# OXCO_DaughterCard_Main.net
KiCad netlist of a schematic drawn in Altium Designer
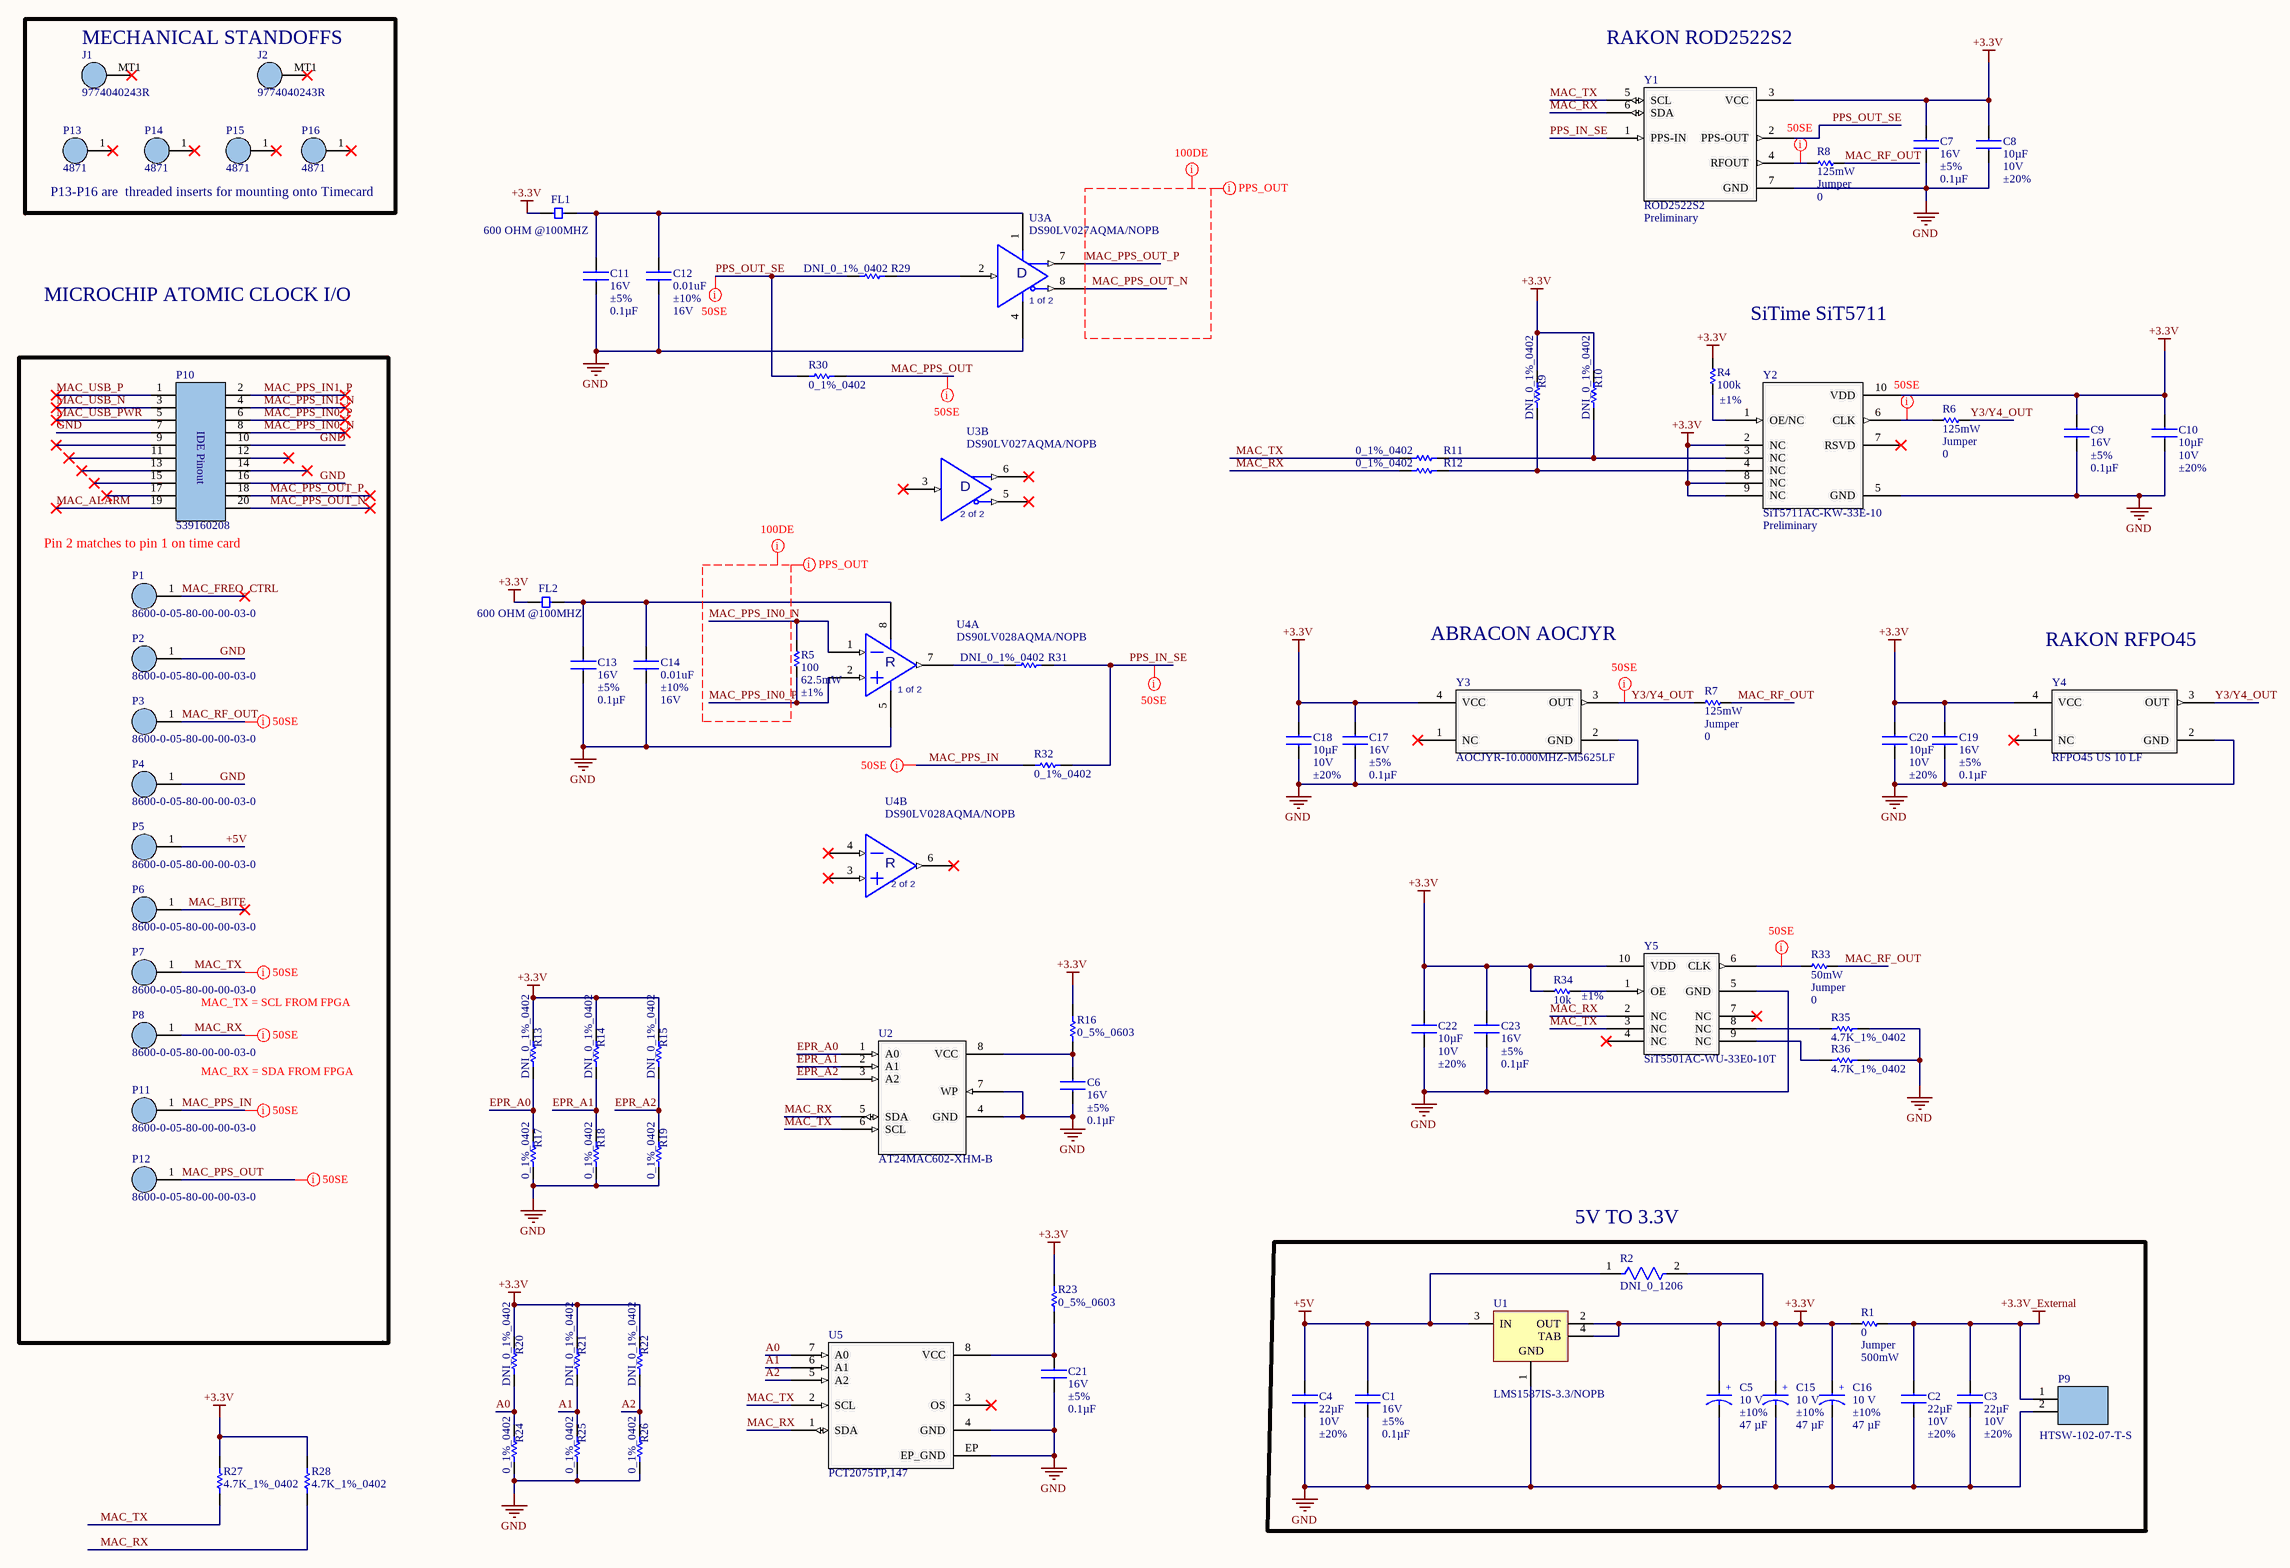
[diagram p0: OXCO_DaughterCard_Main.schdoc]

(export (version "E")
  (design (tool "Eeschema 10.0.6"))
  (components
    (comp (ref "C1")
      (value "Samsung Electro-Mechanics_CL05B104JO5NNNC")
      (footprint "CAPC1005X055N")
      (description "CAP, CER, X7R, 0.1UF, 5%, 16V, 0402, 0.55MM T")
      (fields
        (field (name "MANUFACTURER") "Samsung Electro-Mechanics")
        (field (name "VOLTAGE RATING") "16V")
        (field (name "TOLERANCE") "±5%")
        (field (name "MANUFACTURER PART NUMBER") "CL05B104JO5NNNC")
        (field (name "CAPACITANCE") "0.1µF")
      )
      (libsource (lib "FRL Altium Server") (part "Capacitor_300mil"))
    )
    (comp (ref "C2")
      (value "Murata_GRM21BR61A226ME51L")
      (footprint "CAPC2013X140N")
      (description "CAP, CER, X5R, 22UF, 20%, 10V, 0805, 1.40MM T")
      (fields
        (field (name "CAPACITANCE") "22µF")
        (field (name "VOLTAGE RATING") "10V")
        (field (name "MANUFACTURER PART NUMBER") "GRM21BR61A226ME51L")
        (field (name "TOLERANCE") "±20%")
        (field (name "MANUFACTURER") "Murata")
      )
      (libsource (lib "FRL Altium Server") (part "Capacitor_300mil"))
    )
    (comp (ref "C3")
      (value "Murata_GRM21BR61A226ME51L")
      (footprint "CAPC2013X140N")
      (description "CAP, CER, X5R, 22UF, 20%, 10V, 0805, 1.40MM T")
      (fields
        (field (name "CAPACITANCE") "22µF")
        (field (name "VOLTAGE RATING") "10V")
        (field (name "MANUFACTURER PART NUMBER") "GRM21BR61A226ME51L")
        (field (name "TOLERANCE") "±20%")
        (field (name "MANUFACTURER") "Murata")
      )
      (libsource (lib "FRL Altium Server") (part "Capacitor_300mil"))
    )
    (comp (ref "C4")
      (value "Murata_GRM21BR61A226ME51L")
      (footprint "CAPC2013X140N")
      (description "CAP, CER, X5R, 22UF, 20%, 10V, 0805, 1.40MM T")
      (fields
        (field (name "CAPACITANCE") "22µF")
        (field (name "VOLTAGE RATING") "10V")
        (field (name "MANUFACTURER PART NUMBER") "GRM21BR61A226ME51L")
        (field (name "TOLERANCE") "±20%")
        (field (name "MANUFACTURER") "Murata")
      )
      (libsource (lib "FRL Altium Server") (part "Capacitor_300mil"))
    )
    (comp (ref "C5")
      (value "Kemet_T491B476K010AT")
      (footprint "CAPMP3528X210N_T520")
      (description "CAP TANT 47UF 10% 10V 1411")
      (fields
        (field (name "VOLTAGE RATING") "10 V")
        (field (name "MANUFACTURER PART NUMBER") "T491B476K010AT")
        (field (name "TOLERANCE") "±10%")
        (field (name "CAPACITANCE") "47 µF")
        (field (name "MANUFACTURER") "Kemet")
      )
      (libsource (lib "FRL Altium Server") (part "Capacitor_Polar_300mil"))
    )
    (comp (ref "C6")
      (value "Samsung Electro-Mechanics_CL05B104JO5NNNC")
      (footprint "CAPC1005X055N")
      (description "CAP, CER, X7R, 0.1UF, 5%, 16V, 0402, 0.55MM T")
      (fields
        (field (name "MANUFACTURER") "Samsung Electro-Mechanics")
        (field (name "VOLTAGE RATING") "16V")
        (field (name "TOLERANCE") "±5%")
        (field (name "MANUFACTURER PART NUMBER") "CL05B104JO5NNNC")
        (field (name "CAPACITANCE") "0.1µF")
      )
      (libsource (lib "FRL Altium Server") (part "Capacitor_300mil"))
    )
    (comp (ref "C7")
      (value "Samsung Electro-Mechanics_CL05B104JO5NNNC")
      (footprint "CAPC1005X055N")
      (description "CAP, CER, X7R, 0.1UF, 5%, 16V, 0402, 0.55MM T")
      (fields
        (field (name "MANUFACTURER") "Samsung Electro-Mechanics")
        (field (name "VOLTAGE RATING") "16V")
        (field (name "TOLERANCE") "±5%")
        (field (name "MANUFACTURER PART NUMBER") "CL05B104JO5NNNC")
        (field (name "CAPACITANCE") "0.1µF")
      )
      (libsource (lib "FRL Altium Server") (part "Capacitor_300mil"))
    )
    (comp (ref "C8")
      (value "Murata_GRM188D71A106MA73D")
      (footprint "CAPC1608X100N")
      (description "CAP, CER, X7T, 10UF, 20%, 10V, 0603, 1.00MM T")
      (fields
        (field (name "MANUFACTURER PART NUMBER") "GRM188D71A106MA73D")
        (field (name "CAPACITANCE") "10µF")
        (field (name "VOLTAGE RATING") "10V")
        (field (name "MANUFACTURER") "Murata")
        (field (name "TOLERANCE") "±20%")
      )
      (libsource (lib "FRL Altium Server") (part "Capacitor_300mil"))
    )
    (comp (ref "C9")
      (value "Samsung Electro-Mechanics_CL05B104JO5NNNC")
      (footprint "CAPC1005X055N")
      (description "CAP, CER, X7R, 0.1UF, 5%, 16V, 0402, 0.55MM T")
      (fields
        (field (name "MANUFACTURER") "Samsung Electro-Mechanics")
        (field (name "VOLTAGE RATING") "16V")
        (field (name "TOLERANCE") "±5%")
        (field (name "MANUFACTURER PART NUMBER") "CL05B104JO5NNNC")
        (field (name "CAPACITANCE") "0.1µF")
      )
      (libsource (lib "FRL Altium Server") (part "Capacitor_300mil"))
    )
    (comp (ref "C10")
      (value "Murata_GRM188D71A106MA73D")
      (footprint "CAPC1608X100N")
      (description "CAP, CER, X7T, 10UF, 20%, 10V, 0603, 1.00MM T")
      (fields
        (field (name "MANUFACTURER PART NUMBER") "GRM188D71A106MA73D")
        (field (name "CAPACITANCE") "10µF")
        (field (name "VOLTAGE RATING") "10V")
        (field (name "MANUFACTURER") "Murata")
        (field (name "TOLERANCE") "±20%")
      )
      (libsource (lib "FRL Altium Server") (part "Capacitor_300mil"))
    )
    (comp (ref "C11")
      (value "Samsung Electro-Mechanics_CL05B104JO5NNNC")
      (footprint "CAPC1005X055N")
      (description "CAP, CER, X7R, 0.1UF, 5%, 16V, 0402, 0.55MM T")
      (fields
        (field (name "MANUFACTURER") "Samsung Electro-Mechanics")
        (field (name "VOLTAGE RATING") "16V")
        (field (name "TOLERANCE") "±5%")
        (field (name "MANUFACTURER PART NUMBER") "CL05B104JO5NNNC")
        (field (name "CAPACITANCE") "0.1µF")
      )
      (libsource (lib "FRL Altium Server") (part "Capacitor_300mil"))
    )
    (comp (ref "C12")
      (value "Yageo_CC0402KRX7R7BB103")
      (footprint "CAPC1005X055N")
      (description "CAP, CER, X7R, 0.01UF, 10%, 16V, 0402, 0.55MM T")
      (fields
        (field (name "MANUFACTURER") "Yageo")
        (field (name "CAPACITANCE") "0.01uF")
        (field (name "TOLERANCE") "±10%")
        (field (name "MANUFACTURER PART NUMBER") "CC0402KRX7R7BB103")
        (field (name "VOLTAGE RATING") "16V")
      )
      (libsource (lib "FRL Altium Server") (part "Capacitor_300mil"))
    )
    (comp (ref "C13")
      (value "Samsung Electro-Mechanics_CL05B104JO5NNNC")
      (footprint "CAPC1005X055N")
      (description "CAP, CER, X7R, 0.1UF, 5%, 16V, 0402, 0.55MM T")
      (fields
        (field (name "MANUFACTURER") "Samsung Electro-Mechanics")
        (field (name "VOLTAGE RATING") "16V")
        (field (name "TOLERANCE") "±5%")
        (field (name "MANUFACTURER PART NUMBER") "CL05B104JO5NNNC")
        (field (name "CAPACITANCE") "0.1µF")
      )
      (libsource (lib "FRL Altium Server") (part "Capacitor_300mil"))
    )
    (comp (ref "C14")
      (value "Yageo_CC0402KRX7R7BB103")
      (footprint "CAPC1005X055N")
      (description "CAP, CER, X7R, 0.01UF, 10%, 16V, 0402, 0.55MM T")
      (fields
        (field (name "MANUFACTURER") "Yageo")
        (field (name "CAPACITANCE") "0.01uF")
        (field (name "TOLERANCE") "±10%")
        (field (name "MANUFACTURER PART NUMBER") "CC0402KRX7R7BB103")
        (field (name "VOLTAGE RATING") "16V")
      )
      (libsource (lib "FRL Altium Server") (part "Capacitor_300mil"))
    )
    (comp (ref "C15")
      (value "Kemet_T491B476K010AT")
      (footprint "CAPMP3528X210N_T520")
      (description "CAP TANT 47UF 10% 10V 1411")
      (fields
        (field (name "VOLTAGE RATING") "10 V")
        (field (name "MANUFACTURER PART NUMBER") "T491B476K010AT")
        (field (name "TOLERANCE") "±10%")
        (field (name "CAPACITANCE") "47 µF")
        (field (name "MANUFACTURER") "Kemet")
      )
      (libsource (lib "FRL Altium Server") (part "Capacitor_Polar_300mil"))
    )
    (comp (ref "C16")
      (value "Kemet_T491B476K010AT")
      (footprint "CAPMP3528X210N_T520")
      (description "CAP TANT 47UF 10% 10V 1411")
      (fields
        (field (name "VOLTAGE RATING") "10 V")
        (field (name "MANUFACTURER PART NUMBER") "T491B476K010AT")
        (field (name "TOLERANCE") "±10%")
        (field (name "CAPACITANCE") "47 µF")
        (field (name "MANUFACTURER") "Kemet")
      )
      (libsource (lib "FRL Altium Server") (part "Capacitor_Polar_300mil"))
    )
    (comp (ref "C17")
      (value "Samsung Electro-Mechanics_CL05B104JO5NNNC")
      (footprint "CAPC1005X055N")
      (description "CAP, CER, X7R, 0.1UF, 5%, 16V, 0402, 0.55MM T")
      (fields
        (field (name "MANUFACTURER") "Samsung Electro-Mechanics")
        (field (name "VOLTAGE RATING") "16V")
        (field (name "TOLERANCE") "±5%")
        (field (name "MANUFACTURER PART NUMBER") "CL05B104JO5NNNC")
        (field (name "CAPACITANCE") "0.1µF")
      )
      (libsource (lib "FRL Altium Server") (part "Capacitor_300mil"))
    )
    (comp (ref "C18")
      (value "Murata_GRM188D71A106MA73D")
      (footprint "CAPC1608X100N")
      (description "CAP, CER, X7T, 10UF, 20%, 10V, 0603, 1.00MM T")
      (fields
        (field (name "MANUFACTURER PART NUMBER") "GRM188D71A106MA73D")
        (field (name "CAPACITANCE") "10µF")
        (field (name "VOLTAGE RATING") "10V")
        (field (name "MANUFACTURER") "Murata")
        (field (name "TOLERANCE") "±20%")
      )
      (libsource (lib "FRL Altium Server") (part "Capacitor_300mil"))
    )
    (comp (ref "C19")
      (value "Samsung Electro-Mechanics_CL05B104JO5NNNC")
      (footprint "CAPC1005X055N")
      (description "CAP, CER, X7R, 0.1UF, 5%, 16V, 0402, 0.55MM T")
      (fields
        (field (name "MANUFACTURER") "Samsung Electro-Mechanics")
        (field (name "VOLTAGE RATING") "16V")
        (field (name "TOLERANCE") "±5%")
        (field (name "MANUFACTURER PART NUMBER") "CL05B104JO5NNNC")
        (field (name "CAPACITANCE") "0.1µF")
      )
      (libsource (lib "FRL Altium Server") (part "Capacitor_300mil"))
    )
    (comp (ref "C20")
      (value "Murata_GRM188D71A106MA73D")
      (footprint "CAPC1608X100N")
      (description "CAP, CER, X7T, 10UF, 20%, 10V, 0603, 1.00MM T")
      (fields
        (field (name "MANUFACTURER PART NUMBER") "GRM188D71A106MA73D")
        (field (name "CAPACITANCE") "10µF")
        (field (name "VOLTAGE RATING") "10V")
        (field (name "MANUFACTURER") "Murata")
        (field (name "TOLERANCE") "±20%")
      )
      (libsource (lib "FRL Altium Server") (part "Capacitor_300mil"))
    )
    (comp (ref "C21")
      (value "Samsung Electro-Mechanics_CL05B104JO5NNNC")
      (footprint "CAPC1005X055N")
      (description "CAP, CER, X7R, 0.1UF, 5%, 16V, 0402, 0.55MM T")
      (fields
        (field (name "MANUFACTURER") "Samsung Electro-Mechanics")
        (field (name "VOLTAGE RATING") "16V")
        (field (name "TOLERANCE") "±5%")
        (field (name "MANUFACTURER PART NUMBER") "CL05B104JO5NNNC")
        (field (name "CAPACITANCE") "0.1µF")
      )
      (libsource (lib "FRL Altium Server") (part "Capacitor_300mil"))
    )
    (comp (ref "C22")
      (value "Murata_GRM188R61A106ME69D")
      (footprint "CAPC1608X090N")
      (description "CAP, CER, X5R, 10UF, 20%, 10V, 0603, 0.80MM T")
      (fields
        (field (name "MANUFACTURER PART NUMBER") "GRM188R61A106ME69D")
        (field (name "CAPACITANCE") "10µF")
        (field (name "VOLTAGE RATING") "10V")
        (field (name "MANUFACTURER") "Murata")
        (field (name "TOLERANCE") "±20%")
      )
      (libsource (lib "Meta RLR Altium Enterprise Server") (part "Capacitor_300mil"))
    )
    (comp (ref "C23")
      (value "Samsung Electro-Mechanics_CL05B104JO5NNNC")
      (footprint "CAPC1005X055N")
      (description "CAP, CER, X7R, 0.1UF, 5%, 16V, 0402, 0.55MM T")
      (fields
        (field (name "MANUFACTURER") "Samsung Electro-Mechanics")
        (field (name "VOLTAGE RATING") "16V")
        (field (name "TOLERANCE") "±5%")
        (field (name "MANUFACTURER PART NUMBER") "CL05B104JO5NNNC")
        (field (name "CAPACITANCE") "0.1µF")
      )
      (libsource (lib "Meta RLR Altium Enterprise Server") (part "Capacitor_300mil"))
    )
    (comp (ref "FL1")
      (value "TDK_MPZ1608S601ATA00")
      (footprint "INDC1608X095N")
      (description "FERRITE BEAD, 600 OHM @100MHZ, 25%, 1A, 0.150 OHM DCR, 0603, 0.95MM T")
      (fields
        (field (name "MANUFACTURER PART NUMBER") "MPZ1608S601ATA00")
        (field (name "TOLERANCE") "0.25%")
        (field (name "IMPEDANCE @ FREQUENCY") "600 OHM @100MHZ")
      )
      (libsource (lib "FRL Altium Server") (part "FerriteBead_300mil"))
    )
    (comp (ref "FL2")
      (value "TDK_MPZ1608S601ATA00")
      (footprint "INDC1608X095N")
      (description "FERRITE BEAD, 600 OHM @100MHZ, 25%, 1A, 0.150 OHM DCR, 0603, 0.95MM T")
      (fields
        (field (name "MANUFACTURER PART NUMBER") "MPZ1608S601ATA00")
        (field (name "TOLERANCE") "0.25%")
        (field (name "IMPEDANCE @ FREQUENCY") "600 OHM @100MHZ")
      )
      (libsource (lib "FRL Altium Server") (part "FerriteBead_300mil"))
    )
    (comp (ref "J1")
      (value "Wurth_9774040243R")
      (footprint "TH000V_300DIAx400_001mt_9774040243R")
      (description "STANDOFF, ROUND, M2X0.4 STEEL 4MM, 9774040243R")
      (fields
        (field (name "MANUFACTURER PART NUMBER") "9774040243R")
        (field (name "MANUFACTURER") "Wurth Elektronik")
      )
      (libsource (lib "FRL Altium Server") (part "CONN_SR_000pin_001mt_RND_F"))
    )
    (comp (ref "J2")
      (value "Wurth_9774040243R")
      (footprint "TH000V_300DIAx400_001mt_9774040243R")
      (description "STANDOFF, ROUND, M2X0.4 STEEL 4MM, 9774040243R")
      (fields
        (field (name "MANUFACTURER PART NUMBER") "9774040243R")
        (field (name "MANUFACTURER") "Wurth Elektronik")
      )
      (libsource (lib "FRL Altium Server") (part "CONN_SR_000pin_001mt_RND_F"))
    )
    (comp (ref "P1")
      (value "Mill-Max_8600-0-05-80-00-00-03-0")
      (footprint "TH001V_109DIA_000mt_8600-0")
      (description "CONN, PC PIN, PRESS-FIT, 10.16MM LENGTH, TIN, TH")
      (fields
        (field (name "MANUFACTURER PART NUMBER") "8600-0-05-80-00-00-03-0")
        (field (name "MANUFACTURER") "Mill-Max Manufacturing Corp.")
      )
      (libsource (lib "FRL Altium Server") (part "CONN_SR_001pin_000mt_RND_M"))
    )
    (comp (ref "P2")
      (value "Mill-Max_8600-0-05-80-00-00-03-0")
      (footprint "TH001V_109DIA_000mt_8600-0")
      (description "CONN, PC PIN, PRESS-FIT, 10.16MM LENGTH, TIN, TH")
      (fields
        (field (name "MANUFACTURER PART NUMBER") "8600-0-05-80-00-00-03-0")
        (field (name "MANUFACTURER") "Mill-Max Manufacturing Corp.")
      )
      (libsource (lib "FRL Altium Server") (part "CONN_SR_001pin_000mt_RND_M"))
    )
    (comp (ref "P3")
      (value "Mill-Max_8600-0-05-80-00-00-03-0")
      (footprint "TH001V_109DIA_000mt_8600-0")
      (description "CONN, PC PIN, PRESS-FIT, 10.16MM LENGTH, TIN, TH")
      (fields
        (field (name "MANUFACTURER PART NUMBER") "8600-0-05-80-00-00-03-0")
        (field (name "MANUFACTURER") "Mill-Max Manufacturing Corp.")
      )
      (libsource (lib "FRL Altium Server") (part "CONN_SR_001pin_000mt_RND_M"))
    )
    (comp (ref "P4")
      (value "Mill-Max_8600-0-05-80-00-00-03-0")
      (footprint "TH001V_109DIA_000mt_8600-0")
      (description "CONN, PC PIN, PRESS-FIT, 10.16MM LENGTH, TIN, TH")
      (fields
        (field (name "MANUFACTURER PART NUMBER") "8600-0-05-80-00-00-03-0")
        (field (name "MANUFACTURER") "Mill-Max Manufacturing Corp.")
      )
      (libsource (lib "FRL Altium Server") (part "CONN_SR_001pin_000mt_RND_M"))
    )
    (comp (ref "P5")
      (value "Mill-Max_8600-0-05-80-00-00-03-0")
      (footprint "TH001V_109DIA_000mt_8600-0")
      (description "CONN, PC PIN, PRESS-FIT, 10.16MM LENGTH, TIN, TH")
      (fields
        (field (name "MANUFACTURER PART NUMBER") "8600-0-05-80-00-00-03-0")
        (field (name "MANUFACTURER") "Mill-Max Manufacturing Corp.")
      )
      (libsource (lib "FRL Altium Server") (part "CONN_SR_001pin_000mt_RND_M"))
    )
    (comp (ref "P6")
      (value "Mill-Max_8600-0-05-80-00-00-03-0")
      (footprint "TH001V_109DIA_000mt_8600-0")
      (description "CONN, PC PIN, PRESS-FIT, 10.16MM LENGTH, TIN, TH")
      (fields
        (field (name "MANUFACTURER PART NUMBER") "8600-0-05-80-00-00-03-0")
        (field (name "MANUFACTURER") "Mill-Max Manufacturing Corp.")
      )
      (libsource (lib "FRL Altium Server") (part "CONN_SR_001pin_000mt_RND_M"))
    )
    (comp (ref "P7")
      (value "Mill-Max_8600-0-05-80-00-00-03-0")
      (footprint "TH001V_109DIA_000mt_8600-0")
      (description "CONN, PC PIN, PRESS-FIT, 10.16MM LENGTH, TIN, TH")
      (fields
        (field (name "MANUFACTURER PART NUMBER") "8600-0-05-80-00-00-03-0")
        (field (name "MANUFACTURER") "Mill-Max Manufacturing Corp.")
      )
      (libsource (lib "FRL Altium Server") (part "CONN_SR_001pin_000mt_RND_M"))
    )
    (comp (ref "P8")
      (value "Mill-Max_8600-0-05-80-00-00-03-0")
      (footprint "TH001V_109DIA_000mt_8600-0")
      (description "CONN, PC PIN, PRESS-FIT, 10.16MM LENGTH, TIN, TH")
      (fields
        (field (name "MANUFACTURER PART NUMBER") "8600-0-05-80-00-00-03-0")
        (field (name "MANUFACTURER") "Mill-Max Manufacturing Corp.")
      )
      (libsource (lib "FRL Altium Server") (part "CONN_SR_001pin_000mt_RND_M"))
    )
    (comp (ref "P9")
      (value "Samtec_HTSW-102-07-T-S")
      (footprint "TH002_254_508x254x838_000mt_HTSW")
      (description "CONN, PIN, HEADER, 2POS, 2.54MM PITCH, 8.38MM H, VERT, TIN, TH")
      (fields
        (field (name "MANUFACTURER") "Samtec Inc.")
        (field (name "MANUFACTURER PART NUMBER") "HTSW-102-07-T-S")
      )
      (libsource (lib "FRL Altium Server") (part "CONN_SR_002pin_000mt_M"))
    )
    (comp (ref "P10")
      (value "Molex_539160208")
      (footprint "SM020V_50_730x310x337_000mt_53916")
      (description "CONN, B2B/FPC, HEADER, 20-POS, 0.5MM PITCH, 4.0MM H, VERT, GOLD, SMT")
      (fields (field (name "MANUFACTURER") "Molex") (field (name "MANUFACTURER PART NUMBER") "539160208"))
      (libsource (lib "FRL Altium Server") (part "CONN_DR_020pin_000mt_M"))
    )
    (comp (ref "P11")
      (value "Mill-Max_8600-0-05-80-00-00-03-0")
      (footprint "TH001V_109DIA_000mt_8600-0")
      (description "CONN, PC PIN, PRESS-FIT, 10.16MM LENGTH, TIN, TH")
      (fields
        (field (name "MANUFACTURER PART NUMBER") "8600-0-05-80-00-00-03-0")
        (field (name "MANUFACTURER") "Mill-Max Manufacturing Corp.")
      )
      (libsource (lib "FRL Altium Server") (part "CONN_SR_001pin_000mt_RND_M"))
    )
    (comp (ref "P12")
      (value "Mill-Max_8600-0-05-80-00-00-03-0")
      (footprint "TH001V_109DIA_000mt_8600-0")
      (description "CONN, PC PIN, PRESS-FIT, 10.16MM LENGTH, TIN, TH")
      (fields
        (field (name "MANUFACTURER PART NUMBER") "8600-0-05-80-00-00-03-0")
        (field (name "MANUFACTURER") "Mill-Max Manufacturing Corp.")
      )
      (libsource (lib "FRL Altium Server") (part "CONN_SR_001pin_000mt_RND_M"))
    )
    (comp (ref "P13")
      (value "4871")
      (footprint "Keystone_4871")
      (description "Round Standoff Threaded #2-56 Steel 0.063\" (1.60mm) 1/16\"")
      (fields (field (name "MANUFACTURER") "Keystone") (field (name "MANUFACTURER PART NUMBER") "4871"))
      (libsource (lib "846-01710_SCH_OCXO_DaughterCard") (part "Keystone_4871"))
    )
    (comp (ref "P14")
      (value "4871")
      (footprint "Keystone_4871")
      (description "Round Standoff Threaded #2-56 Steel 0.063\" (1.60mm) 1/16\"")
      (fields (field (name "MANUFACTURER") "Keystone") (field (name "MANUFACTURER PART NUMBER") "4871"))
      (libsource (lib "846-01710_SCH_OCXO_DaughterCard") (part "Keystone_4871"))
    )
    (comp (ref "P15")
      (value "4871")
      (footprint "Keystone_4871")
      (description "Round Standoff Threaded #2-56 Steel 0.063\" (1.60mm) 1/16\"")
      (fields (field (name "MANUFACTURER") "Keystone") (field (name "MANUFACTURER PART NUMBER") "4871"))
      (libsource (lib "846-01710_SCH_OCXO_DaughterCard") (part "Keystone_4871"))
    )
    (comp (ref "P16")
      (value "4871")
      (footprint "Keystone_4871")
      (description "Round Standoff Threaded #2-56 Steel 0.063\" (1.60mm) 1/16\"")
      (fields (field (name "MANUFACTURER") "Keystone") (field (name "MANUFACTURER PART NUMBER") "4871"))
      (libsource (lib "846-01710_SCH_OCXO_DaughterCard") (part "Keystone_4871"))
    )
    (comp (ref "R1")
      (value "Stackpole Electronics, Inc._RMCF1210ZT0R00")
      (footprint "RESC3225X070N")
      (description "RES, 0.0 OHM, 3A, 1/2W, 1210")
      (fields
        (field (name "MANUFACTURER PART NUMBER") "RMCF1210ZT0R00")
        (field (name "MANUFACTURER") "Stackpole Electronics, Inc.")
        (field (name "RESISTANCE") "0")
        (field (name "TOLERANCE") "Jumper")
        (field (name "POWER (WATTS)") "500mW")
      )
      (libsource (lib "FRL Altium Server") (part "Resistor_300mil"))
    )
    (comp (ref "R2")
      (value "DNI_0_1206")
      (footprint "FP-RC1206-MFG")
      (description "RES SMD 0 OHM JUMPER 1/4W 1206")
      (fields
        (field (name "MANUFACTURER PART NUMBER") "RC1206JR-070RL")
        (field (name "MANUFACTURER") "YAGEO")
      )
      (libsource (lib "Altium Content Vault") (part "1029c3af85768c4190bb7ad29bc67b5"))
    )
    (comp (ref "R4")
      (value "Panasonic_ERJ-2RKF1003X")
      (footprint "RESC1005X040N")
      (description "RES, 100K OHM, 1%, 1/10W, 100PPM/C, 0402")
      (fields
        (field (name "MANUFACTURER PART NUMBER") "ERJ-2RKF1003X")
        (field (name "MANUFACTURER") "Panasonic")
        (field (name "RESISTANCE") "100k")
        (field (name "TOLERANCE") "±1%")
      )
      (libsource (lib "FRL Altium Server") (part "Resistor_300mil"))
    )
    (comp (ref "R5")
      (value "Yageo_RC0402FR-07100RL")
      (footprint "RESC1005X040N")
      (description "RES SMD 100 OHM 1% 1/16W 0402")
      (fields
        (field (name "MANUFACTURER PART NUMBER") "RC0402FR-07100RL")
        (field (name "RESISTANCE") "100")
        (field (name "POWER (WATTS)") "62.5mW")
        (field (name "MANUFACTURER") "Yageo")
        (field (name "TOLERANCE") "±1%")
      )
      (libsource (lib "FRL Altium Server") (part "Resistor_300mil"))
    )
    (comp (ref "R6")
      (value "Stackpole Electronics, Inc._HCJ0402ZT0R00")
      (footprint "RESC1005X045N")
      (description "RES, 0.0 OHM, 1/8W, 6.5A, 0402")
      (fields
        (field (name "POWER (WATTS)") "125mW")
        (field (name "MANUFACTURER PART NUMBER") "HCJ0402ZT0R00")
        (field (name "TOLERANCE") "Jumper")
        (field (name "MANUFACTURER") "Stackpole Electronics, Inc.")
        (field (name "RESISTANCE") "0")
      )
      (libsource (lib "FRL Altium Server") (part "Resistor_300mil"))
    )
    (comp (ref "R7")
      (value "Stackpole Electronics, Inc._HCJ0402ZT0R00")
      (footprint "RESC1005X045N")
      (description "RES, 0.0 OHM, 1/8W, 6.5A, 0402")
      (fields
        (field (name "POWER (WATTS)") "125mW")
        (field (name "MANUFACTURER PART NUMBER") "HCJ0402ZT0R00")
        (field (name "TOLERANCE") "Jumper")
        (field (name "MANUFACTURER") "Stackpole Electronics, Inc.")
        (field (name "RESISTANCE") "0")
      )
      (libsource (lib "FRL Altium Server") (part "Resistor_300mil"))
    )
    (comp (ref "R8")
      (value "Stackpole Electronics, Inc._HCJ0402ZT0R00")
      (footprint "RESC1005X045N")
      (description "RES, 0.0 OHM, 1/8W, 6.5A, 0402")
      (fields
        (field (name "POWER (WATTS)") "125mW")
        (field (name "MANUFACTURER PART NUMBER") "HCJ0402ZT0R00")
        (field (name "TOLERANCE") "Jumper")
        (field (name "MANUFACTURER") "Stackpole Electronics, Inc.")
        (field (name "RESISTANCE") "0")
      )
      (libsource (lib "FRL Altium Server") (part "Resistor_300mil"))
    )
    (comp (ref "R9")
      (value "DNI_0_1%_0402")
      (footprint "RESC1005X40X25NL05T10")
      (fields (field (name "MANUFACTURER") "Yageo / Phycomp") (field (name "PART NUMBER") "RC0402JR-070RL"))
      (libsource (lib "Altium Content Vault") (part "RES"))
    )
    (comp (ref "R10")
      (value "DNI_0_1%_0402")
      (footprint "RESC1005X40X25NL05T10")
      (fields (field (name "MANUFACTURER") "Yageo / Phycomp") (field (name "PART NUMBER") "RC0402JR-070RL"))
      (libsource (lib "Altium Content Vault") (part "RES"))
    )
    (comp (ref "R11")
      (value "0_1%_0402")
      (footprint "RESC1005X40X25NL05T10")
      (fields (field (name "MANUFACTURER") "Yageo / Phycomp") (field (name "PART NUMBER") "RC0402JR-070RL"))
      (libsource (lib "Altium Content Vault") (part "RES"))
    )
    (comp (ref "R12")
      (value "0_1%_0402")
      (footprint "RESC1005X40X25NL05T10")
      (fields (field (name "MANUFACTURER") "Yageo / Phycomp") (field (name "PART NUMBER") "RC0402JR-070RL"))
      (libsource (lib "Altium Content Vault") (part "RES"))
    )
    (comp (ref "R13")
      (value "DNI_0_1%_0402")
      (footprint "RESC1005X40X25NL05T10")
      (fields (field (name "MANUFACTURER") "Yageo / Phycomp") (field (name "PART NUMBER") "RC0402JR-070RL"))
      (libsource (lib "Altium Content Vault") (part "RES"))
    )
    (comp (ref "R14")
      (value "DNI_0_1%_0402")
      (footprint "RESC1005X40X25NL05T10")
      (fields (field (name "MANUFACTURER") "Yageo / Phycomp") (field (name "PART NUMBER") "RC0402JR-070RL"))
      (libsource (lib "Altium Content Vault") (part "RES"))
    )
    (comp (ref "R15")
      (value "DNI_0_1%_0402")
      (footprint "RESC1005X40X25NL05T10")
      (fields (field (name "MANUFACTURER") "Yageo / Phycomp") (field (name "PART NUMBER") "RC0402JR-070RL"))
      (libsource (lib "Altium Content Vault") (part "RES"))
    )
    (comp (ref "R16")
      (value "0_5%_0603")
      (footprint "RESC1608X55X25ML10T15")
      (description "Chip Resistor, 0 Ohm, +/- 5%, 0.1 W, -55 to 155 degC, 0603 (1608 Metric), RoHS, Tape and Reel")
      (fields (field (name "TOLERANCE") "5%") (field (name "MANUFACTURER") "Yageo"))
      (libsource (lib "Altium Content Vault") (part "RES-2"))
    )
    (comp (ref "R17")
      (value "0_1%_0402")
      (footprint "RESC1005X40X25NL05T10")
      (fields (field (name "MANUFACTURER") "Yageo / Phycomp") (field (name "PART NUMBER") "RC0402JR-070RL"))
      (libsource (lib "Altium Content Vault") (part "RES"))
    )
    (comp (ref "R18")
      (value "0_1%_0402")
      (footprint "RESC1005X40X25NL05T10")
      (fields (field (name "MANUFACTURER") "Yageo / Phycomp") (field (name "PART NUMBER") "RC0402JR-070RL"))
      (libsource (lib "Altium Content Vault") (part "RES"))
    )
    (comp (ref "R19")
      (value "0_1%_0402")
      (footprint "RESC1005X40X25NL05T10")
      (fields (field (name "MANUFACTURER") "Yageo / Phycomp") (field (name "PART NUMBER") "RC0402JR-070RL"))
      (libsource (lib "Altium Content Vault") (part "RES"))
    )
    (comp (ref "R20")
      (value "DNI_0_1%_0402")
      (footprint "RESC1005X40X25NL05T10")
      (fields (field (name "MANUFACTURER") "Yageo / Phycomp") (field (name "PART NUMBER") "RC0402JR-070RL"))
      (libsource (lib "Altium Content Vault") (part "RES"))
    )
    (comp (ref "R21")
      (value "DNI_0_1%_0402")
      (footprint "RESC1005X40X25NL05T10")
      (fields (field (name "MANUFACTURER") "Yageo / Phycomp") (field (name "PART NUMBER") "RC0402JR-070RL"))
      (libsource (lib "Altium Content Vault") (part "RES"))
    )
    (comp (ref "R22")
      (value "DNI_0_1%_0402")
      (footprint "RESC1005X40X25NL05T10")
      (fields (field (name "MANUFACTURER") "Yageo / Phycomp") (field (name "PART NUMBER") "RC0402JR-070RL"))
      (libsource (lib "Altium Content Vault") (part "RES"))
    )
    (comp (ref "R23")
      (value "0_5%_0603")
      (footprint "RESC1608X55X25ML10T15")
      (description "Chip Resistor, 0 Ohm, +/- 5%, 0.1 W, -55 to 155 degC, 0603 (1608 Metric), RoHS, Tape and Reel")
      (fields (field (name "TOLERANCE") "5%") (field (name "MANUFACTURER") "Yageo"))
      (libsource (lib "Altium Content Vault") (part "RES-2"))
    )
    (comp (ref "R24")
      (value "0_1%_0402")
      (footprint "RESC1005X40X25NL05T10")
      (fields (field (name "MANUFACTURER") "Yageo / Phycomp") (field (name "PART NUMBER") "RC0402JR-070RL"))
      (libsource (lib "Altium Content Vault") (part "RES"))
    )
    (comp (ref "R25")
      (value "0_1%_0402")
      (footprint "RESC1005X40X25NL05T10")
      (fields (field (name "MANUFACTURER") "Yageo / Phycomp") (field (name "PART NUMBER") "RC0402JR-070RL"))
      (libsource (lib "Altium Content Vault") (part "RES"))
    )
    (comp (ref "R26")
      (value "0_1%_0402")
      (footprint "RESC1005X40X25NL05T10")
      (fields (field (name "MANUFACTURER") "Yageo / Phycomp") (field (name "PART NUMBER") "RC0402JR-070RL"))
      (libsource (lib "Altium Content Vault") (part "RES"))
    )
    (comp (ref "R27")
      (value "4.7K_1%_0402")
      (footprint "RESC1005X40X25LL05T05")
      (description "Chip Resistor, 4.7 KOhm, +/- 1%, 0.1 W, -55 to 155 degC, 0402 (1005 Metric), RoHS, Tape and Reel")
      (fields (field (name "TOLERANCE") "1%") (field (name "PARTNUMBER") "ERJ-2RKF4701X"))
      (libsource (lib "Altium Content Vault") (part "RES-2"))
    )
    (comp (ref "R28")
      (value "4.7K_1%_0402")
      (footprint "RESC1005X40X25LL05T05")
      (description "Chip Resistor, 4.7 KOhm, +/- 1%, 0.1 W, -55 to 155 degC, 0402 (1005 Metric), RoHS, Tape and Reel")
      (fields (field (name "TOLERANCE") "1%") (field (name "PARTNUMBER") "ERJ-2RKF4701X"))
      (libsource (lib "Altium Content Vault") (part "RES-2"))
    )
    (comp (ref "R29")
      (value "DNI_0_1%_0402")
      (footprint "RESC1005X40X25NL05T10")
      (fields (field (name "MANUFACTURER") "Yageo / Phycomp") (field (name "PART NUMBER") "RC0402JR-070RL"))
      (libsource (lib "Altium Content Vault") (part "RES"))
    )
    (comp (ref "R30")
      (value "0_1%_0402")
      (footprint "RESC1005X40X25NL05T10")
      (fields (field (name "MANUFACTURER") "Yageo / Phycomp") (field (name "PART NUMBER") "RC0402JR-070RL"))
      (libsource (lib "Altium Content Vault") (part "RES"))
    )
    (comp (ref "R31")
      (value "DNI_0_1%_0402")
      (footprint "RESC1005X40X25NL05T10")
      (fields (field (name "MANUFACTURER") "Yageo / Phycomp") (field (name "PART NUMBER") "RC0402JR-070RL"))
      (libsource (lib "Altium Content Vault") (part "RES"))
    )
    (comp (ref "R32")
      (value "0_1%_0402")
      (footprint "RESC1005X40X25NL05T10")
      (fields (field (name "MANUFACTURER") "Yageo / Phycomp") (field (name "PART NUMBER") "RC0402JR-070RL"))
      (libsource (lib "Altium Content Vault") (part "RES"))
    )
    (comp (ref "R33")
      (value "Yageo_RC0201JR-070RL")
      (footprint "RESC0603X026N")
      (description "RES, 0.0 OHM, 0.5A, 1/20W, 0201")
      (fields
        (field (name "POWER (WATTS)") "50mW")
        (field (name "MANUFACTURER PART NUMBER") "RC0201JR-070RL")
        (field (name "TOLERANCE") "Jumper")
        (field (name "MANUFACTURER") "Yageo")
        (field (name "RESISTANCE") "0")
      )
      (libsource (lib "Meta RLR Altium Enterprise Server") (part "Resistor_300mil"))
    )
    (comp (ref "R34")
      (value "Yageo_RC0201FR-0710KL")
      (footprint "RESC0603X026N")
      (description "RES, 10K OHM, 1%, 1/20W, 200PPM/C, 0201")
      (fields
        (field (name "MANUFACTURER") "Yageo")
        (field (name "MANUFACTURER PART NUMBER") "RC0201FR-0710KL")
        (field (name "RESISTANCE") "10k")
        (field (name "TOLERANCE") "±1%")
      )
      (libsource (lib "Meta RLR Altium Enterprise Server") (part "Resistor_300mil"))
    )
    (comp (ref "R35")
      (value "4.7K_1%_0402")
      (footprint "RESC1005X40X25LL05T05")
      (description "Chip Resistor, 4.7 KOhm, +/- 1%, 0.1 W, -55 to 155 degC, 0402 (1005 Metric), RoHS, Tape and Reel")
      (fields (field (name "TOLERANCE") "1%") (field (name "PARTNUMBER") "ERJ-2RKF4701X"))
      (libsource (lib "Altium Content Vault") (part "RES-2"))
    )
    (comp (ref "R36")
      (value "4.7K_1%_0402")
      (footprint "RESC1005X40X25LL05T05")
      (description "Chip Resistor, 4.7 KOhm, +/- 1%, 0.1 W, -55 to 155 degC, 0402 (1005 Metric), RoHS, Tape and Reel")
      (fields (field (name "TOLERANCE") "1%") (field (name "PARTNUMBER") "ERJ-2RKF4701X"))
      (libsource (lib "Altium Content Vault") (part "RES-2"))
    )
    (comp (ref "U1")
      (value "LMS1587IS-3.3/NOPB")
      (footprint "KTT0003B_L")
      (description "3A Low Dropout Fast Response Regulators, 3-pin TO-263, Pb-Free")
      (fields (field (name "MANUFACTURER") "Texas Instruments"))
      (libsource (lib "Altium Content Vault") (part "PM-REG-LM1086-SOT4"))
    )
    (comp (ref "U2")
      (value "Microchip_AT24MAC602-XHM-B")
      (footprint "TSSOP65P640X120-8N")
      (description "IC, EEPROM, AT24MAC602, 2K-BIT (256 X 8), 1MHZ, I2C, 1.7V - 5.5V, TSSOP-8")
      (fields
        (field (name "MANUFACTURER") "Microchip Technology")
        (field (name "MANUFACTURER PART NUMBER") "AT24MAC602-XHM-B")
      )
      (libsource (lib "FRL Altium Server") (part "IC_EEPROM_8pins_3ADD_A"))
    )
    (comp (ref "U3")
      (value "TI_DS90LV027AQMA/NOPB")
      (footprint "SOP127P600X175_8N")
      (description "IC, DRIVER, DS90LV027AQ, DUAL, DIFF, LVDS, 600MBPS, SOIC-8")
      (fields
        (field (name "MANUFACTURER PART NUMBER") "DS90LV027AQMA/NOPB")
        (field (name "MANUFACTURER") "Texas Instruments")
      )
      (libsource (lib "FRL Altium Server") (part "IC_DRVR_8P_LVDS_0R-2D"))
    )
    (comp (ref "U4")
      (value "TI_DS90LV028AQMA/NOPB")
      (footprint "SOP127P600X175_8N")
      (description "IC, RVCR, DS90LV028AQ-Q1, DUAL, DIFF, LVDS, 400MBPS, SOIC-8")
      (fields
        (field (name "MANUFACTURER PART NUMBER") "DS90LV028AQMA/NOPB")
        (field (name "MANUFACTURER") "Texas Instruments")
      )
      (libsource (lib "FRL Altium Server") (part "IC_RCVR_8P_LVDS_2R-0D"))
    )
    (comp (ref "U5")
      (value "NXP_PCT2075TP,147")
      (footprint "SON50P300X200X80-HS-9N_EP160x160_IPC")
      (description "SENSOR DIGITAL -55C-125C 8HWSON")
      (fields
        (field (name "MANUFACTURER") "NXP USA Inc.")
        (field (name "MANUFACTURER PART NUMBER") "PCT2075TP,147")
      )
      (libsource (lib "FRL Altium Server") (part "IC_SNS_8pins_1EP_PCT2075"))
    )
    (comp (ref "Y1")
      (value "Rakon_ROD2522S2")
      (footprint "OSC007_762_2540x2200x1230")
      (description "OSC, OCXO, 10MHZ - 20MHZ, 0.5PPB STAB, 3.3V, 22.0X25.4X12.3MM, SMT")
      (fields
        (field (name "MANUFACTURER PART NUMBER") "ROD2522S2")
        (field (name "PART STATUS") "Preliminary")
        (field (name "MANUFACTURER") "Rakon")
      )
      (libsource (lib "FRL Altium Server") (part "OSC_7Pins_I2C"))
    )
    (comp (ref "Y2")
      (value "SiTime_SiT5711AC-KW-33E-10")
      (footprint "SON150P700X619-10N_SiT5711")
      (description "OSC, OCXO, 10.000MHZ, 5PPM STAB, LVCMOS/CLIPPED SINE, 3.3V, DFN-10")
      (fields
        (field (name "MANUFACTURER") "SiTime")
        (field (name "MANUFACTURER PART NUMBER") "SiT5711AC-KW-33E-10")
        (field (name "PART STATUS") "Preliminary")
      )
      (libsource (lib "FRL Altium Server") (part "OSC_10Pins_OE_LVCMOS"))
    )
    (comp (ref "Y3")
      (value "Abracon_AOCJYR-10.000MHZ-M5625LF")
      (footprint "OSC004_600_970x750x410_AOCJYR")
      (description "OSC, OCXO, 10.000MHZ, 25PPB STAB, LVCMOS, 3.3V, 9.7X7.5X4.3MM, SMT")
      (fields
        (field (name "MANUFACTURER PART NUMBER") "AOCJYR-10.000MHZ-M5625LF")
        (field (name "MANUFACTURER") "Abracon LLC")
      )
      (libsource (lib "FRL Altium Server") (part "OSC_4Pins_001NC_001out_001gnd_001vcc_000mt"))
    )
    (comp (ref "Y4")
      (value "Rakon_RFPO45 US 10 LF")
      (footprint "OSC004_600_970x750x430_RFP045")
      (description "OSC, OCXO, RFPO45, 10 - 26MHZ, 10PPB STAB, HCMOS, 3.3V, 9.7X7.5X4.3MM, SMT")
      (fields
        (field (name "MANUFACTURER PART NUMBER") "RFPO45 US 10 LF")
        (field (name "MANUFACTURER") "Rakon")
      )
      (libsource (lib "FRL Altium Server") (part "OSC_4Pins_001NC_001out_001gnd_001vcc_000mt"))
    )
    (comp (ref "Y5")
      (value "SiTime_SiT5501AC-WU-33E0-10T")
      (footprint "SITIME_SPL-086-CQFN-010-C07050_REV_DRAFT")
      (description "OSC, MEMS, STRATUM 3E, 10.000MHZ, 10PPB STAB, LVCMOS, 3.3V, O/P EN, 7.0X5.0X2.2MM, CQFN-10")
      (fields
        (field (name "MANUFACTURER PART NUMBER") "SiT5501AC-WU-33E0-10T")
        (field (name "MANUFACTURER") "SiTime")
      )
      (libsource (lib "Meta RLR Altium Enterprise Server") (part "SiT5501AC-WU-33E0-10T_010pin"))
    )
  )
  (nets
    (net (code "1") (name "+3.3V") (class "Default")
      (node (ref "C10") (pin "1") (pinfunction "1_1") (pintype "passive"))
      (node (ref "C15") (pin "1") (pinfunction "1_1") (pintype "passive"))
      (node (ref "C16") (pin "1") (pinfunction "1_1") (pintype "passive"))
      (node (ref "C17") (pin "1") (pinfunction "1_1") (pintype "passive"))
      (node (ref "C18") (pin "1") (pinfunction "1_1") (pintype "passive"))
      (node (ref "C19") (pin "1") (pinfunction "1_1") (pintype "passive"))
      (node (ref "C20") (pin "1") (pinfunction "1_1") (pintype "passive"))
      (node (ref "C22") (pin "1") (pinfunction "1_1") (pintype "passive"))
      (node (ref "C23") (pin "1") (pinfunction "1_1") (pintype "passive"))
      (node (ref "C5") (pin "1") (pinfunction "1_1") (pintype "passive"))
      (node (ref "C7") (pin "1") (pinfunction "1_1") (pintype "passive"))
      (node (ref "C8") (pin "1") (pinfunction "1_1") (pintype "passive"))
      (node (ref "C9") (pin "1") (pinfunction "1_1") (pintype "passive"))
      (node (ref "FL1") (pin "1") (pinfunction "1_1") (pintype "passive"))
      (node (ref "FL2") (pin "1") (pinfunction "1_1") (pintype "passive"))
      (node (ref "R1") (pin "1") (pinfunction "1_1") (pintype "passive"))
      (node (ref "R10") (pin "1") (pinfunction "1_1") (pintype "passive"))
      (node (ref "R13") (pin "1") (pinfunction "1_1") (pintype "passive"))
      (node (ref "R14") (pin "1") (pinfunction "1_1") (pintype "passive"))
      (node (ref "R15") (pin "1") (pinfunction "1_1") (pintype "passive"))
      (node (ref "R16") (pin "2") (pinfunction "2_2") (pintype "passive"))
      (node (ref "R2") (pin "2") (pinfunction "2_2") (pintype "passive"))
      (node (ref "R20") (pin "1") (pinfunction "1_1") (pintype "passive"))
      (node (ref "R21") (pin "1") (pinfunction "1_1") (pintype "passive"))
      (node (ref "R22") (pin "1") (pinfunction "1_1") (pintype "passive"))
      (node (ref "R23") (pin "2") (pinfunction "2_2") (pintype "passive"))
      (node (ref "R27") (pin "2") (pinfunction "2_2") (pintype "passive"))
      (node (ref "R28") (pin "2") (pinfunction "2_2") (pintype "passive"))
      (node (ref "R34") (pin "1") (pinfunction "1_1") (pintype "passive"))
      (node (ref "R4") (pin "1") (pinfunction "1_1") (pintype "passive"))
      (node (ref "R9") (pin "1") (pinfunction "1_1") (pintype "passive"))
      (node (ref "U1") (pin "2") (pinfunction "OUT_2") (pintype "power_in"))
      (node (ref "U1") (pin "4") (pinfunction "TAB_4") (pintype "power_in"))
      (node (ref "Y1") (pin "3") (pinfunction "VCC_3") (pintype "power_in"))
      (node (ref "Y2") (pin "10") (pinfunction "VDD_10") (pintype "power_in"))
      (node (ref "Y2") (pin "2") (pinfunction "NC_2") (pintype "passive"))
      (node (ref "Y2") (pin "8") (pinfunction "NC_8") (pintype "passive"))
      (node (ref "Y2") (pin "9") (pinfunction "NC_9") (pintype "passive"))
      (node (ref "Y3") (pin "4") (pinfunction "VCC_4") (pintype "power_in"))
      (node (ref "Y4") (pin "4") (pinfunction "VCC_4") (pintype "power_in"))
      (node (ref "Y5") (pin "10") (pinfunction "VDD_10") (pintype "power_in"))
    )
    (net (code "2") (name "+3.3V_External") (class "Default")
      (node (ref "C2") (pin "1") (pinfunction "1_1") (pintype "passive"))
      (node (ref "C3") (pin "1") (pinfunction "1_1") (pintype "passive"))
      (node (ref "P9") (pin "1") (pinfunction "1_1") (pintype "passive"))
      (node (ref "R1") (pin "2") (pinfunction "2_2") (pintype "passive"))
    )
    (net (code "3") (name "+5V") (class "Default")
      (node (ref "C1") (pin "1") (pinfunction "1_1") (pintype "passive"))
      (node (ref "C4") (pin "1") (pinfunction "1_1") (pintype "passive"))
      (node (ref "P5") (pin "1") (pinfunction "1_1") (pintype "passive"))
      (node (ref "R2") (pin "1") (pinfunction "1_1") (pintype "passive"))
      (node (ref "U1") (pin "3") (pinfunction "IN_3") (pintype "power_in"))
    )
    (net (code "4") (name "/A0") (class "Default")
      (node (ref "R20") (pin "2") (pinfunction "2_2") (pintype "passive"))
      (node (ref "R24") (pin "1") (pinfunction "1_1") (pintype "passive"))
      (node (ref "U5") (pin "7") (pinfunction "A0_7") (pintype "input"))
    )
    (net (code "5") (name "/A1") (class "Default")
      (node (ref "R21") (pin "2") (pinfunction "2_2") (pintype "passive"))
      (node (ref "R25") (pin "1") (pinfunction "1_1") (pintype "passive"))
      (node (ref "U5") (pin "6") (pinfunction "A1_6") (pintype "input"))
    )
    (net (code "6") (name "/A2") (class "Default")
      (node (ref "R22") (pin "2") (pinfunction "2_2") (pintype "passive"))
      (node (ref "R26") (pin "1") (pinfunction "1_1") (pintype "passive"))
      (node (ref "U5") (pin "5") (pinfunction "A2_5") (pintype "input"))
    )
    (net (code "7") (name "/EPR_A0") (class "Default")
      (node (ref "R13") (pin "2") (pinfunction "2_2") (pintype "passive"))
      (node (ref "R17") (pin "1") (pinfunction "1_1") (pintype "passive"))
      (node (ref "U2") (pin "1") (pinfunction "A0_1") (pintype "input"))
    )
    (net (code "8") (name "/EPR_A1") (class "Default")
      (node (ref "R14") (pin "2") (pinfunction "2_2") (pintype "passive"))
      (node (ref "R18") (pin "1") (pinfunction "1_1") (pintype "passive"))
      (node (ref "U2") (pin "2") (pinfunction "A1_2") (pintype "input"))
    )
    (net (code "9") (name "/EPR_A2") (class "Default")
      (node (ref "R15") (pin "2") (pinfunction "2_2") (pintype "passive"))
      (node (ref "R19") (pin "1") (pinfunction "1_1") (pintype "passive"))
      (node (ref "U2") (pin "3") (pinfunction "A2_3") (pintype "input"))
    )
    (net (code "10") (name "/MAC_ALARM") (class "Default")
      (node (ref "P10") (pin "19") (pinfunction "19_19") (pintype "passive+no_connect"))
    )
    (net (code "11") (name "/MAC_BITE") (class "Default")
      (node (ref "P6") (pin "1") (pinfunction "1_1") (pintype "passive+no_connect"))
    )
    (net (code "12") (name "/MAC_FREQ_CTRL") (class "Default")
      (node (ref "P1") (pin "1") (pinfunction "1_1") (pintype "passive+no_connect"))
    )
    (net (code "13") (name "/MAC_PPS_IN") (class "Default")
      (node (ref "P11") (pin "1") (pinfunction "1_1") (pintype "passive"))
      (node (ref "R32") (pin "1") (pinfunction "1_1") (pintype "passive"))
    )
    (net (code "14") (name "/MAC_PPS_IN0_N") (class "Default")
      (node (ref "P10") (pin "8") (pinfunction "8_8") (pintype "passive"))
      (node (ref "R5") (pin "1") (pinfunction "1_1") (pintype "passive"))
      (node (ref "U4") (pin "1") (pinfunction "RIN1-_1") (pintype "input"))
    )
    (net (code "15") (name "/MAC_PPS_IN0_P") (class "Default")
      (node (ref "P10") (pin "6") (pinfunction "6_6") (pintype "passive"))
      (node (ref "R5") (pin "2") (pinfunction "2_2") (pintype "passive"))
      (node (ref "U4") (pin "2") (pinfunction "RIN1+_2") (pintype "input"))
    )
    (net (code "16") (name "/MAC_PPS_IN1_N") (class "Default")
      (node (ref "P10") (pin "4") (pinfunction "4_4") (pintype "passive+no_connect"))
    )
    (net (code "17") (name "/MAC_PPS_IN1_P") (class "Default")
      (node (ref "P10") (pin "2") (pinfunction "2_2") (pintype "passive+no_connect"))
    )
    (net (code "18") (name "/MAC_PPS_OUT") (class "Default")
      (node (ref "P12") (pin "1") (pinfunction "1_1") (pintype "passive"))
      (node (ref "R30") (pin "2") (pinfunction "2_2") (pintype "passive"))
    )
    (net (code "19") (name "/MAC_PPS_OUT_N") (class "Default")
      (node (ref "P10") (pin "20") (pinfunction "20_20") (pintype "passive"))
      (node (ref "U3") (pin "8") (pinfunction "DO-1_8") (pintype "output"))
    )
    (net (code "20") (name "/MAC_PPS_OUT_P") (class "Default")
      (node (ref "P10") (pin "18") (pinfunction "18_18") (pintype "passive"))
      (node (ref "U3") (pin "7") (pinfunction "DO+1_7") (pintype "output"))
    )
    (net (code "21") (name "/MAC_RF_OUT") (class "Default")
      (node (ref "P3") (pin "1") (pinfunction "1_1") (pintype "passive"))
      (node (ref "R33") (pin "2") (pinfunction "2_2") (pintype "passive"))
      (node (ref "R7") (pin "2") (pinfunction "2_2") (pintype "passive"))
      (node (ref "R8") (pin "2") (pinfunction "2_2") (pintype "passive"))
    )
    (net (code "22") (name "/MAC_RX") (class "Default")
      (node (ref "P8") (pin "1") (pinfunction "1_1") (pintype "passive"))
      (node (ref "R12") (pin "1") (pinfunction "1_1") (pintype "passive"))
      (node (ref "R28") (pin "1") (pinfunction "1_1") (pintype "passive"))
      (node (ref "U2") (pin "5") (pinfunction "SDA_5") (pintype "bidirectional"))
      (node (ref "U5") (pin "1") (pinfunction "SDA_1") (pintype "bidirectional"))
      (node (ref "Y1") (pin "6") (pinfunction "SDA_6") (pintype "bidirectional"))
      (node (ref "Y5") (pin "2") (pinfunction "NC_2") (pintype "passive"))
    )
    (net (code "23") (name "/MAC_TX") (class "Default")
      (node (ref "P7") (pin "1") (pinfunction "1_1") (pintype "passive"))
      (node (ref "R11") (pin "1") (pinfunction "1_1") (pintype "passive"))
      (node (ref "R27") (pin "1") (pinfunction "1_1") (pintype "passive"))
      (node (ref "U2") (pin "6") (pinfunction "SCL_6") (pintype "input"))
      (node (ref "U5") (pin "2") (pinfunction "SCL_2") (pintype "input"))
      (node (ref "Y1") (pin "5") (pinfunction "SCL_5") (pintype "bidirectional"))
      (node (ref "Y5") (pin "3") (pinfunction "NC_3") (pintype "passive"))
    )
    (net (code "24") (name "/MAC_USB_N") (class "Default")
      (node (ref "P10") (pin "3") (pinfunction "3_3") (pintype "passive+no_connect"))
    )
    (net (code "25") (name "/MAC_USB_P") (class "Default")
      (node (ref "P10") (pin "1") (pinfunction "1_1") (pintype "passive+no_connect"))
    )
    (net (code "26") (name "/MAC_USB_PWR") (class "Default")
      (node (ref "P10") (pin "5") (pinfunction "5_5") (pintype "passive+no_connect"))
    )
    (net (code "27") (name "/PPS_IN_SE") (class "Default")
      (node (ref "R31") (pin "2") (pinfunction "2_2") (pintype "passive"))
      (node (ref "R32") (pin "2") (pinfunction "2_2") (pintype "passive"))
      (node (ref "Y1") (pin "1") (pinfunction "PPS-IN_1") (pintype "input"))
    )
    (net (code "28") (name "/PPS_OUT_SE") (class "Default")
      (node (ref "R29") (pin "1") (pinfunction "1_1") (pintype "passive"))
      (node (ref "R30") (pin "1") (pinfunction "1_1") (pintype "passive"))
      (node (ref "Y1") (pin "2") (pinfunction "PPS-OUT_2") (pintype "output"))
    )
    (net (code "29") (name "/Y3{slash}Y4_OUT") (class "Default")
      (node (ref "R6") (pin "2") (pinfunction "2_2") (pintype "passive"))
      (node (ref "R7") (pin "1") (pinfunction "1_1") (pintype "passive"))
      (node (ref "Y3") (pin "3") (pinfunction "OUT_3") (pintype "output"))
      (node (ref "Y4") (pin "3") (pinfunction "OUT_3") (pintype "output"))
    )
    (net (code "30") (name "GND") (class "Default")
      (node (ref "C1") (pin "2") (pinfunction "2_2") (pintype "passive"))
      (node (ref "C10") (pin "2") (pinfunction "2_2") (pintype "passive"))
      (node (ref "C11") (pin "2") (pinfunction "2_2") (pintype "passive"))
      (node (ref "C12") (pin "2") (pinfunction "2_2") (pintype "passive"))
      (node (ref "C13") (pin "2") (pinfunction "2_2") (pintype "passive"))
      (node (ref "C14") (pin "2") (pinfunction "2_2") (pintype "passive"))
      (node (ref "C15") (pin "2") (pinfunction "2_2") (pintype "passive"))
      (node (ref "C16") (pin "2") (pinfunction "2_2") (pintype "passive"))
      (node (ref "C17") (pin "2") (pinfunction "2_2") (pintype "passive"))
      (node (ref "C18") (pin "2") (pinfunction "2_2") (pintype "passive"))
      (node (ref "C19") (pin "2") (pinfunction "2_2") (pintype "passive"))
      (node (ref "C2") (pin "2") (pinfunction "2_2") (pintype "passive"))
      (node (ref "C20") (pin "2") (pinfunction "2_2") (pintype "passive"))
      (node (ref "C21") (pin "2") (pinfunction "2_2") (pintype "passive"))
      (node (ref "C22") (pin "2") (pinfunction "2_2") (pintype "passive"))
      (node (ref "C23") (pin "2") (pinfunction "2_2") (pintype "passive"))
      (node (ref "C3") (pin "2") (pinfunction "2_2") (pintype "passive"))
      (node (ref "C4") (pin "2") (pinfunction "2_2") (pintype "passive"))
      (node (ref "C5") (pin "2") (pinfunction "2_2") (pintype "passive"))
      (node (ref "C6") (pin "2") (pinfunction "2_2") (pintype "passive"))
      (node (ref "C7") (pin "2") (pinfunction "2_2") (pintype "passive"))
      (node (ref "C8") (pin "2") (pinfunction "2_2") (pintype "passive"))
      (node (ref "C9") (pin "2") (pinfunction "2_2") (pintype "passive"))
      (node (ref "P10") (pin "10") (pinfunction "10_10") (pintype "passive"))
      (node (ref "P10") (pin "16") (pinfunction "16_16") (pintype "passive"))
      (node (ref "P10") (pin "7") (pinfunction "7_7") (pintype "passive"))
      (node (ref "P2") (pin "1") (pinfunction "1_1") (pintype "passive"))
      (node (ref "P4") (pin "1") (pinfunction "1_1") (pintype "passive"))
      (node (ref "P9") (pin "2") (pinfunction "2_2") (pintype "passive"))
      (node (ref "R17") (pin "2") (pinfunction "2_2") (pintype "passive"))
      (node (ref "R18") (pin "2") (pinfunction "2_2") (pintype "passive"))
      (node (ref "R19") (pin "2") (pinfunction "2_2") (pintype "passive"))
      (node (ref "R24") (pin "2") (pinfunction "2_2") (pintype "passive"))
      (node (ref "R25") (pin "2") (pinfunction "2_2") (pintype "passive"))
      (node (ref "R26") (pin "2") (pinfunction "2_2") (pintype "passive"))
      (node (ref "R35") (pin "1") (pinfunction "1_1") (pintype "passive"))
      (node (ref "R36") (pin "1") (pinfunction "1_1") (pintype "passive"))
      (node (ref "U1") (pin "1") (pinfunction "GND_1") (pintype "power_in"))
      (node (ref "U2") (pin "4") (pinfunction "GND_4") (pintype "power_in"))
      (node (ref "U2") (pin "7") (pinfunction "WP_7") (pintype "input"))
      (node (ref "U3") (pin "4") (pinfunction "GND_4") (pintype "power_in"))
      (node (ref "U4") (pin "5") (pinfunction "GND_5") (pintype "power_in"))
      (node (ref "U5") (pin "4") (pinfunction "GND_4") (pintype "power_in"))
      (node (ref "U5") (pin "EP") (pinfunction "EP_GND_EP") (pintype "power_in"))
      (node (ref "Y1") (pin "7") (pinfunction "GND_7") (pintype "power_in"))
      (node (ref "Y2") (pin "5") (pinfunction "GND_5") (pintype "power_in"))
      (node (ref "Y3") (pin "2") (pinfunction "GND_2") (pintype "power_in"))
      (node (ref "Y4") (pin "2") (pinfunction "GND_2") (pintype "power_in"))
      (node (ref "Y5") (pin "5") (pinfunction "GND_5") (pintype "power_in"))
    )
    (net (code "31") (name "Net-(R10-Pad2)") (class "Default")
      (node (ref "R10") (pin "2") (pinfunction "2_2") (pintype "passive"))
      (node (ref "R11") (pin "2") (pinfunction "2_2") (pintype "passive"))
      (node (ref "Y2") (pin "3") (pinfunction "NC_3") (pintype "passive"))
    )
    (net (code "32") (name "Net-(R12-Pad2)") (class "Default")
      (node (ref "R12") (pin "2") (pinfunction "2_2") (pintype "passive"))
      (node (ref "R9") (pin "2") (pinfunction "2_2") (pintype "passive"))
      (node (ref "Y2") (pin "4") (pinfunction "NC_4") (pintype "passive"))
    )
    (net (code "33") (name "Net-(R35-Pad2)") (class "Default")
      (node (ref "R35") (pin "2") (pinfunction "2_2") (pintype "passive"))
      (node (ref "Y5") (pin "8") (pinfunction "NC_8") (pintype "passive"))
    )
    (net (code "34") (name "Net-(R36-Pad2)") (class "Default")
      (node (ref "R36") (pin "2") (pinfunction "2_2") (pintype "passive"))
      (node (ref "Y5") (pin "9") (pinfunction "NC_9") (pintype "passive"))
    )
    (net (code "35") (name "Net-(U2-VCC)") (class "Default")
      (node (ref "C6") (pin "1") (pinfunction "1_1") (pintype "passive"))
      (node (ref "R16") (pin "1") (pinfunction "1_1") (pintype "passive"))
      (node (ref "U2") (pin "8") (pinfunction "VCC_8") (pintype "power_in"))
    )
    (net (code "36") (name "Net-(U3A-DI1)") (class "Default")
      (node (ref "R29") (pin "2") (pinfunction "2_2") (pintype "passive"))
      (node (ref "U3") (pin "2") (pinfunction "DI1_2") (pintype "input"))
    )
    (net (code "37") (name "Net-(U3A-VCC)") (class "Default")
      (node (ref "C11") (pin "1") (pinfunction "1_1") (pintype "passive"))
      (node (ref "C12") (pin "1") (pinfunction "1_1") (pintype "passive"))
      (node (ref "FL1") (pin "2") (pinfunction "2_2") (pintype "passive"))
      (node (ref "U3") (pin "1") (pinfunction "VCC_1") (pintype "power_in"))
    )
    (net (code "38") (name "Net-(U4A-ROUT1)") (class "Default")
      (node (ref "R31") (pin "1") (pinfunction "1_1") (pintype "passive"))
      (node (ref "U4") (pin "7") (pinfunction "ROUT1_7") (pintype "output"))
    )
    (net (code "39") (name "Net-(U4A-VCC)") (class "Default")
      (node (ref "C13") (pin "1") (pinfunction "1_1") (pintype "passive"))
      (node (ref "C14") (pin "1") (pinfunction "1_1") (pintype "passive"))
      (node (ref "FL2") (pin "2") (pinfunction "2_2") (pintype "passive"))
      (node (ref "U4") (pin "8") (pinfunction "VCC_8") (pintype "power_in"))
    )
    (net (code "40") (name "Net-(U5-VCC)") (class "Default")
      (node (ref "C21") (pin "1") (pinfunction "1_1") (pintype "passive"))
      (node (ref "R23") (pin "1") (pinfunction "1_1") (pintype "passive"))
      (node (ref "U5") (pin "8") (pinfunction "VCC_8") (pintype "power_in"))
    )
    (net (code "41") (name "Net-(Y1-RFOUT)") (class "Default")
      (node (ref "R8") (pin "1") (pinfunction "1_1") (pintype "passive"))
      (node (ref "Y1") (pin "4") (pinfunction "RFOUT_4") (pintype "output"))
    )
    (net (code "42") (name "Net-(Y2-CLK)") (class "Default")
      (node (ref "R6") (pin "1") (pinfunction "1_1") (pintype "passive"))
      (node (ref "Y2") (pin "6") (pinfunction "CLK_6") (pintype "output"))
    )
    (net (code "43") (name "Net-(Y2-OE{slash}NC)") (class "Default")
      (node (ref "R4") (pin "2") (pinfunction "2_2") (pintype "passive"))
      (node (ref "Y2") (pin "1") (pinfunction "OE/NC_1") (pintype "input"))
    )
    (net (code "44") (name "Net-(Y5-CLK)") (class "Default")
      (node (ref "R33") (pin "1") (pinfunction "1_1") (pintype "passive"))
      (node (ref "Y5") (pin "6") (pinfunction "CLK_6") (pintype "output"))
    )
    (net (code "45") (name "Net-(Y5-OE)") (class "Default")
      (node (ref "R34") (pin "2") (pinfunction "2_2") (pintype "passive"))
      (node (ref "Y5") (pin "1") (pinfunction "OE_1") (pintype "input"))
    )
    (net (code "46") (name "unconnected-(J1-PadMT1)") (class "Default")
      (node (ref "J1") (pin "MT1") (pinfunction "MT1_MT1") (pintype "passive+no_connect"))
    )
    (net (code "47") (name "unconnected-(J2-PadMT1)") (class "Default")
      (node (ref "J2") (pin "MT1") (pinfunction "MT1_MT1") (pintype "passive+no_connect"))
    )
    (net (code "48") (name "unconnected-(P10-Pad9)") (class "Default")
      (node (ref "P10") (pin "9") (pinfunction "9_9") (pintype "passive+no_connect"))
    )
    (net (code "49") (name "unconnected-(P10-Pad11)") (class "Default")
      (node (ref "P10") (pin "11") (pinfunction "11_11") (pintype "passive+no_connect"))
    )
    (net (code "50") (name "unconnected-(P10-Pad12)") (class "Default")
      (node (ref "P10") (pin "12") (pinfunction "12_12") (pintype "passive+no_connect"))
    )
    (net (code "51") (name "unconnected-(P10-Pad13)") (class "Default")
      (node (ref "P10") (pin "13") (pinfunction "13_13") (pintype "passive+no_connect"))
    )
    (net (code "52") (name "unconnected-(P10-Pad14)") (class "Default")
      (node (ref "P10") (pin "14") (pinfunction "14_14") (pintype "passive+no_connect"))
    )
    (net (code "53") (name "unconnected-(P10-Pad15)") (class "Default")
      (node (ref "P10") (pin "15") (pinfunction "15_15") (pintype "passive+no_connect"))
    )
    (net (code "54") (name "unconnected-(P10-Pad17)") (class "Default")
      (node (ref "P10") (pin "17") (pinfunction "17_17") (pintype "passive+no_connect"))
    )
    (net (code "55") (name "unconnected-(P13-Pad1)") (class "Default")
      (node (ref "P13") (pin "1") (pinfunction "1_1") (pintype "passive+no_connect"))
    )
    (net (code "56") (name "unconnected-(P14-Pad1)") (class "Default")
      (node (ref "P14") (pin "1") (pinfunction "1_1") (pintype "passive+no_connect"))
    )
    (net (code "57") (name "unconnected-(P15-Pad1)") (class "Default")
      (node (ref "P15") (pin "1") (pinfunction "1_1") (pintype "passive+no_connect"))
    )
    (net (code "58") (name "unconnected-(P16-Pad1)") (class "Default")
      (node (ref "P16") (pin "1") (pinfunction "1_1") (pintype "passive+no_connect"))
    )
    (net (code "59") (name "unconnected-(U3B-DI2-Pad3)") (class "Default")
      (node (ref "U3") (pin "3") (pinfunction "DI2_3") (pintype "input+no_connect"))
    )
    (net (code "60") (name "unconnected-(U3B-DO+2-Pad6)") (class "Default")
      (node (ref "U3") (pin "6") (pinfunction "DO+2_6") (pintype "output+no_connect"))
    )
    (net (code "61") (name "unconnected-(U3B-DO-2-Pad5)") (class "Default")
      (node (ref "U3") (pin "5") (pinfunction "DO-2_5") (pintype "output+no_connect"))
    )
    (net (code "62") (name "unconnected-(U4B-RIN2+-Pad3)") (class "Default")
      (node (ref "U4") (pin "3") (pinfunction "RIN2+_3") (pintype "input+no_connect"))
    )
    (net (code "63") (name "unconnected-(U4B-RIN2--Pad4)") (class "Default")
      (node (ref "U4") (pin "4") (pinfunction "RIN2-_4") (pintype "input+no_connect"))
    )
    (net (code "64") (name "unconnected-(U4B-ROUT2-Pad6)") (class "Default")
      (node (ref "U4") (pin "6") (pinfunction "ROUT2_6") (pintype "output+no_connect"))
    )
    (net (code "65") (name "unconnected-(U5-OS-Pad3)") (class "Default")
      (node (ref "U5") (pin "3") (pinfunction "OS_3") (pintype "passive+no_connect"))
    )
    (net (code "66") (name "unconnected-(Y2-RSVD-Pad7)") (class "Default")
      (node (ref "Y2") (pin "7") (pinfunction "RSVD_7") (pintype "passive+no_connect"))
    )
    (net (code "67") (name "unconnected-(Y3-NC-Pad1)") (class "Default")
      (node (ref "Y3") (pin "1") (pinfunction "NC_1") (pintype "passive+no_connect"))
    )
    (net (code "68") (name "unconnected-(Y4-NC-Pad1)") (class "Default")
      (node (ref "Y4") (pin "1") (pinfunction "NC_1") (pintype "passive+no_connect"))
    )
    (net (code "69") (name "unconnected-(Y5-NC-Pad4)") (class "Default")
      (node (ref "Y5") (pin "4") (pinfunction "NC_4") (pintype "passive+no_connect"))
    )
    (net (code "70") (name "unconnected-(Y5-NC-Pad7)") (class "Default")
      (node (ref "Y5") (pin "7") (pinfunction "NC_7") (pintype "passive+no_connect"))
    )
  )
)
